# mysensor.net
KiCad netlist of a schematic drawn in EAGLE
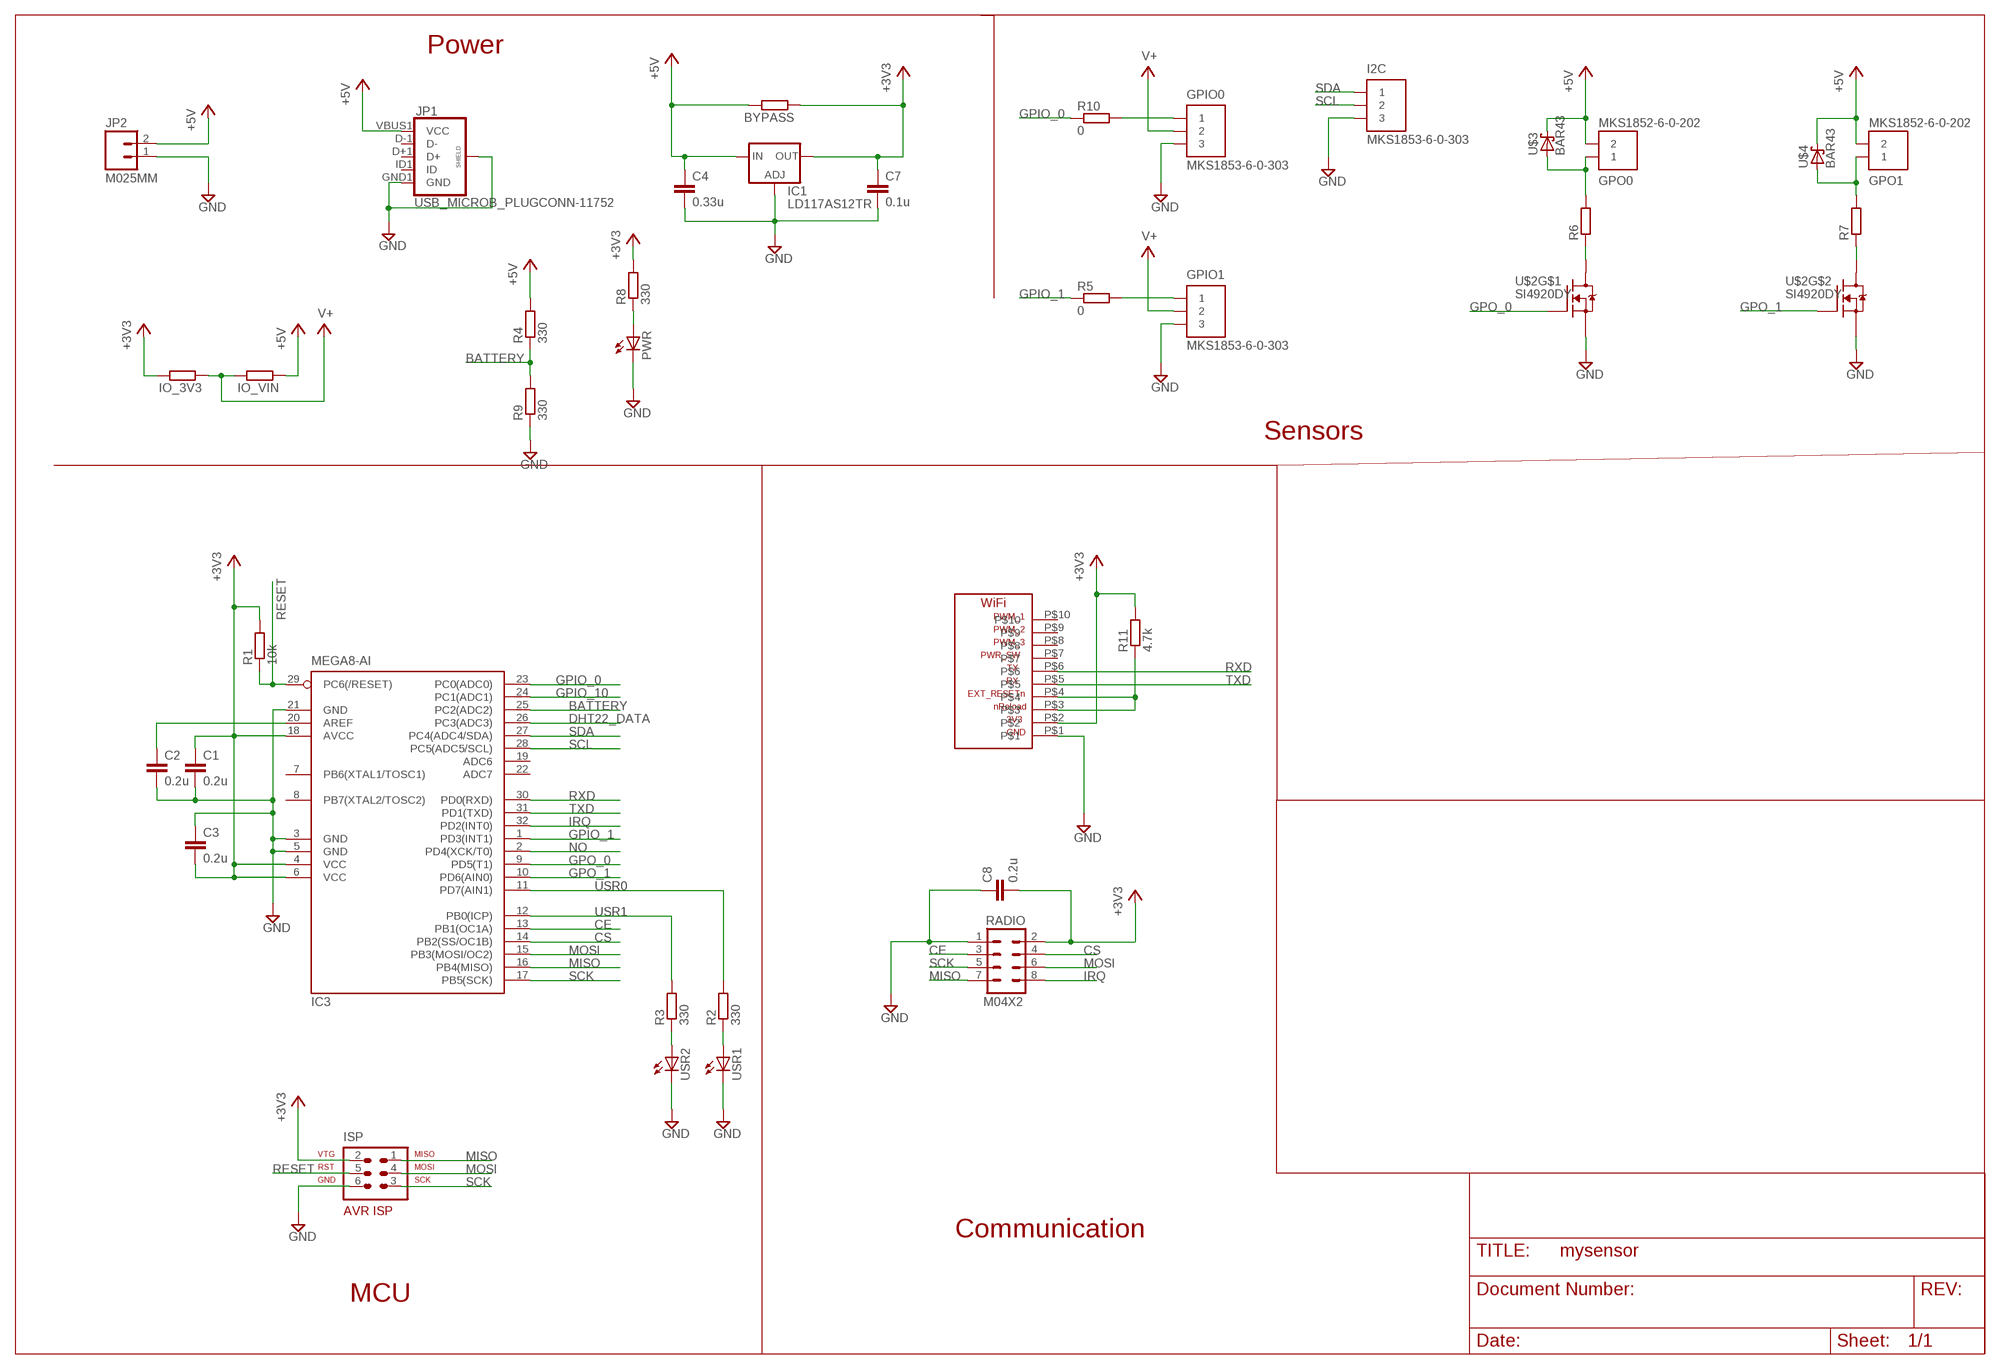
[diagram p0: schematic, sheet 1]

(export (version "E")
  (design (tool "Eeschema 10.0.6"))
  (components
    (comp (ref "BYPASS")
      (value "R-EU_M0805")
      (footprint "eagle-import:M0805")
      (libsource (lib "eagle-import") (part "R-EU_M0805"))
    )
    (comp (ref "C1")
      (value "0.2u")
      (footprint "eagle-import:C0805")
      (libsource (lib "eagle-import") (part "C-EUC0805"))
    )
    (comp (ref "C2")
      (value "0.2u")
      (footprint "eagle-import:C0805")
      (libsource (lib "eagle-import") (part "C-EUC0805"))
    )
    (comp (ref "C3")
      (value "0.2u")
      (footprint "eagle-import:C0805")
      (libsource (lib "eagle-import") (part "C-EUC0805"))
    )
    (comp (ref "C4")
      (value "0.33u")
      (footprint "eagle-import:C0805")
      (libsource (lib "eagle-import") (part "C-EUC0805"))
    )
    (comp (ref "C7")
      (value "0.1u")
      (footprint "eagle-import:C0805")
      (libsource (lib "eagle-import") (part "C-EUC0805"))
    )
    (comp (ref "C8")
      (value "0.2u")
      (footprint "eagle-import:C0805")
      (libsource (lib "eagle-import") (part "C-EUC0805"))
    )
    (comp (ref "GPIO0")
      (value "MKS1853-6-0-303")
      (footprint "eagle-import:MKS1853-6-0-303")
      (libsource (lib "eagle-import") (part "MKS1853-6-0-303"))
    )
    (comp (ref "GPIO1")
      (value "MKS1853-6-0-303")
      (footprint "eagle-import:MKS1853-6-0-303")
      (libsource (lib "eagle-import") (part "MKS1853-6-0-303"))
    )
    (comp (ref "GPO0")
      (value "MKS1852-6-0-202")
      (footprint "eagle-import:MKS1852-6-0-202")
      (libsource (lib "eagle-import") (part "MKS1852-6-0-202"))
    )
    (comp (ref "GPO1")
      (value "MKS1852-6-0-202")
      (footprint "eagle-import:MKS1852-6-0-202")
      (libsource (lib "eagle-import") (part "MKS1852-6-0-202"))
    )
    (comp (ref "I2C")
      (value "MKS1853-6-0-303")
      (footprint "eagle-import:MKS1853-6-0-303")
      (libsource (lib "eagle-import") (part "MKS1853-6-0-303"))
    )
    (comp (ref "IC1")
      (value "LD117AS12TR")
      (footprint "eagle-import:SOT223")
      (libsource (lib "eagle-import") (part "LD117A?S12TR"))
    )
    (comp (ref "IC3")
      (value "MEGA8-AI")
      (footprint "eagle-import:TQFP32-08")
      (fields (field (name "MPN") "ATMEGA8-16AU"))
      (libsource (lib "eagle-import") (part "MEGA8-AI"))
    )
    (comp (ref "IO_3V3")
      (value "R-EU_M0805")
      (footprint "eagle-import:M0805")
      (libsource (lib "eagle-import") (part "R-EU_M0805"))
    )
    (comp (ref "IO_VIN")
      (value "R-EU_M0805")
      (footprint "eagle-import:M0805")
      (libsource (lib "eagle-import") (part "R-EU_M0805"))
    )
    (comp (ref "ISP")
      (value "AVR-ISP-6")
      (footprint "eagle-import:AVR-ISP-6")
      (libsource (lib "eagle-import") (part "AVR-ISP-6"))
    )
    (comp (ref "JP1")
      (value "USB_MICROB_PLUGCONN-11752")
      (footprint "eagle-import:USB-B-MICRO-SMD_V03")
      (libsource (lib "eagle-import") (part "USB_MICROB_PLUGCONN-11752"))
    )
    (comp (ref "JP2")
      (value "M025MM")
      (footprint "eagle-import:SCREWTERMINAL-5MM-2")
      (libsource (lib "eagle-import") (part "M025MM"))
    )
    (comp (ref "PWR")
      (value "LEDCHIP-LED0805")
      (footprint "eagle-import:CHIP-LED0805")
      (libsource (lib "eagle-import") (part "LEDCHIP-LED0805"))
    )
    (comp (ref "R1")
      (value "10k")
      (footprint "eagle-import:R0805")
      (libsource (lib "eagle-import") (part "R-EU_R0805"))
    )
    (comp (ref "R2")
      (value "330")
      (footprint "eagle-import:M0805")
      (libsource (lib "eagle-import") (part "R-EU_M0805"))
    )
    (comp (ref "R3")
      (value "330")
      (footprint "eagle-import:M0805")
      (libsource (lib "eagle-import") (part "R-EU_M0805"))
    )
    (comp (ref "R4")
      (value "330")
      (footprint "eagle-import:M0805")
      (libsource (lib "eagle-import") (part "R-EU_M0805"))
    )
    (comp (ref "R5")
      (value "0")
      (footprint "eagle-import:R0805")
      (libsource (lib "eagle-import") (part "R-EU_R0805"))
    )
    (comp (ref "R6")
      (value "R-EU_M0805")
      (footprint "eagle-import:M0805")
      (libsource (lib "eagle-import") (part "R-EU_M0805"))
    )
    (comp (ref "R7")
      (value "R-EU_M0805")
      (footprint "eagle-import:M0805")
      (libsource (lib "eagle-import") (part "R-EU_M0805"))
    )
    (comp (ref "R8")
      (value "330")
      (footprint "eagle-import:M0805")
      (libsource (lib "eagle-import") (part "R-EU_M0805"))
    )
    (comp (ref "R9")
      (value "330")
      (footprint "eagle-import:M0805")
      (libsource (lib "eagle-import") (part "R-EU_M0805"))
    )
    (comp (ref "R10")
      (value "0")
      (footprint "eagle-import:R0805")
      (libsource (lib "eagle-import") (part "R-EU_R0805"))
    )
    (comp (ref "R11")
      (value "4.7k")
      (footprint "eagle-import:M0805")
      (libsource (lib "eagle-import") (part "R-EU_M0805"))
    )
    (comp (ref "RADIO")
      (value "M04X2")
      (footprint "eagle-import:2X4")
      (libsource (lib "eagle-import") (part "M04X2"))
    )
    (comp (ref "U$1")
      (value "WIFI232")
      (footprint "eagle-import:WLAN")
      (libsource (lib "eagle-import") (part "WIFI232"))
    )
    (comp (ref "U$2")
      (value "SI4920DY")
      (footprint "eagle-import:SO-8")
      (libsource (lib "eagle-import") (part "SI4920DY"))
    )
    (comp (ref "U$3")
      (value "BAR43")
      (footprint "eagle-import:SOT23")
      (libsource (lib "eagle-import") (part "BAR43"))
    )
    (comp (ref "U$4")
      (value "BAR43")
      (footprint "eagle-import:SOT23")
      (libsource (lib "eagle-import") (part "BAR43"))
    )
    (comp (ref "USR1")
      (value "LEDCHIP-LED0805")
      (footprint "eagle-import:CHIP-LED0805")
      (libsource (lib "eagle-import") (part "LEDCHIP-LED0805"))
    )
    (comp (ref "USR2")
      (value "LEDCHIP-LED0805")
      (footprint "eagle-import:CHIP-LED0805")
      (libsource (lib "eagle-import") (part "LEDCHIP-LED0805"))
    )
  )
  (nets
    (net (code "1") (name "+3V3") (class "Default")
      (node (ref "BYPASS") (pin "1") (pinfunction "1_1") (pintype "passive"))
      (node (ref "C1") (pin "1") (pinfunction "1_1") (pintype "passive"))
      (node (ref "C3") (pin "2") (pinfunction "2_2") (pintype "passive"))
      (node (ref "C7") (pin "1") (pinfunction "1_1") (pintype "passive"))
      (node (ref "C8") (pin "2") (pinfunction "2_2") (pintype "passive"))
      (node (ref "IC1") (pin "4") (pinfunction "OUT_4") (pintype "passive"))
      (node (ref "IC3") (pin "18") (pinfunction "AVCC_18") (pintype "power_in"))
      (node (ref "IC3") (pin "4") (pinfunction "VCC_4") (pintype "power_in"))
      (node (ref "IC3") (pin "6") (pinfunction "VCC_6") (pintype "power_in"))
      (node (ref "IO_3V3") (pin "2") (pinfunction "2_2") (pintype "passive"))
      (node (ref "ISP") (pin "2") (pinfunction "2_2") (pintype "passive"))
      (node (ref "R1") (pin "2") (pinfunction "2_2") (pintype "passive"))
      (node (ref "R11") (pin "2") (pinfunction "2_2") (pintype "passive"))
      (node (ref "R8") (pin "2") (pinfunction "2_2") (pintype "passive"))
      (node (ref "RADIO") (pin "2") (pinfunction "2_2") (pintype "passive"))
      (node (ref "U$1") (pin "P$2") (pinfunction "P$2_P$2") (pintype "bidirectional"))
    )
    (net (code "2") (name "+5V") (class "Default")
      (node (ref "BYPASS") (pin "2") (pinfunction "2_2") (pintype "passive"))
      (node (ref "C4") (pin "1") (pinfunction "1_1") (pintype "passive"))
      (node (ref "GPO0") (pin "2") (pinfunction "2_2") (pintype "input"))
      (node (ref "GPO1") (pin "2") (pinfunction "2_2") (pintype "input"))
      (node (ref "IC1") (pin "3") (pinfunction "IN_3") (pintype "input"))
      (node (ref "IO_VIN") (pin "1") (pinfunction "1_1") (pintype "passive"))
      (node (ref "JP1") (pin "VBUS1") (pinfunction "VCC_VBUS1") (pintype "bidirectional"))
      (node (ref "JP2") (pin "2") (pinfunction "2_2") (pintype "passive"))
      (node (ref "R4") (pin "2") (pinfunction "2_2") (pintype "passive"))
      (node (ref "U$3") (pin "3") (pinfunction "C_3") (pintype "passive"))
      (node (ref "U$4") (pin "3") (pinfunction "C_3") (pintype "passive"))
    )
    (net (code "3") (name "/BATTERY") (class "Default")
      (node (ref "IC3") (pin "25") (pinfunction "PC2(ADC2)_25") (pintype "bidirectional"))
      (node (ref "R4") (pin "1") (pinfunction "1_1") (pintype "passive"))
      (node (ref "R9") (pin "2") (pinfunction "2_2") (pintype "passive"))
    )
    (net (code "4") (name "/CE") (class "Default")
      (node (ref "IC3") (pin "13") (pinfunction "PB1(OC1A)_13") (pintype "bidirectional"))
      (node (ref "RADIO") (pin "3") (pinfunction "3_3") (pintype "passive"))
    )
    (net (code "5") (name "/CS") (class "Default")
      (node (ref "IC3") (pin "14") (pinfunction "PB2(SS/OC1B)_14") (pintype "bidirectional"))
      (node (ref "RADIO") (pin "4") (pinfunction "4_4") (pintype "passive"))
    )
    (net (code "6") (name "/DHT22_DATA") (class "Default")
      (node (ref "IC3") (pin "26") (pinfunction "PC3(ADC3)_26") (pintype "bidirectional"))
    )
    (net (code "7") (name "/GPIO_0") (class "Default")
      (node (ref "IC3") (pin "23") (pinfunction "PC0(ADC0)_23") (pintype "bidirectional"))
      (node (ref "R10") (pin "1") (pinfunction "1_1") (pintype "passive"))
    )
    (net (code "8") (name "/GPIO_1") (class "Default")
      (node (ref "IC3") (pin "1") (pinfunction "PD3(INT1)_1") (pintype "bidirectional"))
      (node (ref "R5") (pin "1") (pinfunction "1_1") (pintype "passive"))
    )
    (net (code "9") (name "/GPIO_10") (class "Default")
      (node (ref "IC3") (pin "24") (pinfunction "PC1(ADC1)_24") (pintype "bidirectional"))
    )
    (net (code "10") (name "/GPO_0") (class "Default")
      (node (ref "IC3") (pin "9") (pinfunction "PD5(T1)_9") (pintype "bidirectional"))
      (node (ref "U$2") (pin "2") (pinfunction "G_2") (pintype "passive"))
    )
    (net (code "11") (name "/GPO_1") (class "Default")
      (node (ref "IC3") (pin "10") (pinfunction "PD6(AIN0)_10") (pintype "bidirectional"))
      (node (ref "U$2") (pin "4") (pinfunction "G_4") (pintype "passive"))
    )
    (net (code "12") (name "/IRQ") (class "Default")
      (node (ref "IC3") (pin "32") (pinfunction "PD2(INT0)_32") (pintype "bidirectional"))
      (node (ref "RADIO") (pin "8") (pinfunction "8_8") (pintype "passive"))
    )
    (net (code "13") (name "/MISO") (class "Default")
      (node (ref "IC3") (pin "16") (pinfunction "PB4(MISO)_16") (pintype "bidirectional"))
      (node (ref "ISP") (pin "1") (pinfunction "1_1") (pintype "passive"))
      (node (ref "RADIO") (pin "7") (pinfunction "7_7") (pintype "passive"))
    )
    (net (code "14") (name "/MOSI") (class "Default")
      (node (ref "IC3") (pin "15") (pinfunction "PB3(MOSI/OC2)_15") (pintype "bidirectional"))
      (node (ref "ISP") (pin "4") (pinfunction "4_4") (pintype "passive"))
      (node (ref "RADIO") (pin "6") (pinfunction "6_6") (pintype "passive"))
    )
    (net (code "15") (name "/NO") (class "Default")
      (node (ref "IC3") (pin "2") (pinfunction "PD4(XCK/T0)_2") (pintype "bidirectional"))
    )
    (net (code "16") (name "/RESET") (class "Default")
      (node (ref "IC3") (pin "29") (pinfunction "PC6(/RESET)_29") (pintype "bidirectional"))
      (node (ref "ISP") (pin "5") (pinfunction "5_5") (pintype "passive"))
      (node (ref "R1") (pin "1") (pinfunction "1_1") (pintype "passive"))
    )
    (net (code "17") (name "/RXD") (class "Default")
      (node (ref "IC3") (pin "30") (pinfunction "PD0(RXD)_30") (pintype "bidirectional"))
      (node (ref "U$1") (pin "P$6") (pinfunction "P$6_P$6") (pintype "bidirectional"))
    )
    (net (code "18") (name "/SCK") (class "Default")
      (node (ref "IC3") (pin "17") (pinfunction "PB5(SCK)_17") (pintype "bidirectional"))
      (node (ref "ISP") (pin "3") (pinfunction "3_3") (pintype "passive"))
      (node (ref "RADIO") (pin "5") (pinfunction "5_5") (pintype "passive"))
    )
    (net (code "19") (name "/SCL") (class "Default")
      (node (ref "I2C") (pin "2") (pinfunction "2_2") (pintype "input"))
      (node (ref "IC3") (pin "28") (pinfunction "PC5(ADC5/SCL)_28") (pintype "bidirectional"))
    )
    (net (code "20") (name "/SDA") (class "Default")
      (node (ref "I2C") (pin "1") (pinfunction "1_1") (pintype "input"))
      (node (ref "IC3") (pin "27") (pinfunction "PC4(ADC4/SDA)_27") (pintype "bidirectional"))
    )
    (net (code "21") (name "/TXD") (class "Default")
      (node (ref "IC3") (pin "31") (pinfunction "PD1(TXD)_31") (pintype "bidirectional"))
      (node (ref "U$1") (pin "P$5") (pinfunction "P$5_P$5") (pintype "bidirectional"))
    )
    (net (code "22") (name "/USR0") (class "Default")
      (node (ref "IC3") (pin "11") (pinfunction "PD7(AIN1)_11") (pintype "bidirectional"))
      (node (ref "R2") (pin "2") (pinfunction "2_2") (pintype "passive"))
    )
    (net (code "23") (name "/USR1") (class "Default")
      (node (ref "IC3") (pin "12") (pinfunction "PB0(ICP)_12") (pintype "bidirectional"))
      (node (ref "R3") (pin "2") (pinfunction "2_2") (pintype "passive"))
    )
    (net (code "24") (name "GND") (class "Default")
      (node (ref "C1") (pin "2") (pinfunction "2_2") (pintype "passive"))
      (node (ref "C2") (pin "2") (pinfunction "2_2") (pintype "passive"))
      (node (ref "C3") (pin "1") (pinfunction "1_1") (pintype "passive"))
      (node (ref "C4") (pin "2") (pinfunction "2_2") (pintype "passive"))
      (node (ref "C7") (pin "2") (pinfunction "2_2") (pintype "passive"))
      (node (ref "C8") (pin "1") (pinfunction "1_1") (pintype "passive"))
      (node (ref "GPIO0") (pin "3") (pinfunction "3_3") (pintype "input"))
      (node (ref "GPIO1") (pin "3") (pinfunction "3_3") (pintype "input"))
      (node (ref "I2C") (pin "3") (pinfunction "3_3") (pintype "input"))
      (node (ref "IC1") (pin "1") (pinfunction "ADJ_1") (pintype "input"))
      (node (ref "IC3") (pin "21") (pinfunction "GND_21") (pintype "power_in"))
      (node (ref "IC3") (pin "3") (pinfunction "GND_3") (pintype "power_in"))
      (node (ref "IC3") (pin "5") (pinfunction "GND_5") (pintype "power_in"))
      (node (ref "ISP") (pin "6") (pinfunction "6_6") (pintype "passive"))
      (node (ref "JP1") (pin "GND1") (pinfunction "GND_GND1") (pintype "bidirectional"))
      (node (ref "JP1") (pin "SHIELD1") (pinfunction "SHIELD_SHIELD1") (pintype "bidirectional"))
      (node (ref "JP1") (pin "SHIELD2") (pinfunction "SHIELD_SHIELD2") (pintype "bidirectional"))
      (node (ref "JP1") (pin "SHIELD3") (pinfunction "SHIELD_SHIELD3") (pintype "bidirectional"))
      (node (ref "JP2") (pin "1") (pinfunction "1_1") (pintype "passive"))
      (node (ref "PWR") (pin "C") (pinfunction "C_C") (pintype "passive"))
      (node (ref "R9") (pin "1") (pinfunction "1_1") (pintype "passive"))
      (node (ref "RADIO") (pin "1") (pinfunction "1_1") (pintype "passive"))
      (node (ref "U$1") (pin "P$1") (pinfunction "P$1_P$1") (pintype "bidirectional"))
      (node (ref "U$2") (pin "1") (pinfunction "S_1") (pintype "passive"))
      (node (ref "U$2") (pin "3") (pinfunction "S_3") (pintype "passive"))
      (node (ref "USR1") (pin "C") (pinfunction "C_C") (pintype "passive"))
      (node (ref "USR2") (pin "C") (pinfunction "C_C") (pintype "passive"))
    )
    (net (code "25") (name "Net-(GPIO0-Pad1)") (class "Default")
      (node (ref "GPIO0") (pin "1") (pinfunction "1_1") (pintype "input"))
      (node (ref "R10") (pin "2") (pinfunction "2_2") (pintype "passive"))
    )
    (net (code "26") (name "Net-(GPIO1-Pad1)") (class "Default")
      (node (ref "GPIO1") (pin "1") (pinfunction "1_1") (pintype "input"))
      (node (ref "R5") (pin "2") (pinfunction "2_2") (pintype "passive"))
    )
    (net (code "27") (name "Net-(IC3-AREF)") (class "Default")
      (node (ref "C2") (pin "1") (pinfunction "1_1") (pintype "passive"))
      (node (ref "IC3") (pin "20") (pinfunction "AREF_20") (pintype "passive"))
    )
    (net (code "28") (name "Net-(PWR-PadA)") (class "Default")
      (node (ref "PWR") (pin "A") (pinfunction "A_A") (pintype "passive"))
      (node (ref "R8") (pin "1") (pinfunction "1_1") (pintype "passive"))
    )
    (net (code "29") (name "Net-(R2-Pad1)") (class "Default")
      (node (ref "R2") (pin "1") (pinfunction "1_1") (pintype "passive"))
      (node (ref "USR1") (pin "A") (pinfunction "A_A") (pintype "passive"))
    )
    (net (code "30") (name "Net-(R3-Pad1)") (class "Default")
      (node (ref "R3") (pin "1") (pinfunction "1_1") (pintype "passive"))
      (node (ref "USR2") (pin "A") (pinfunction "A_A") (pintype "passive"))
    )
    (net (code "31") (name "Net-(R11-Pad1)") (class "Default")
      (node (ref "R11") (pin "1") (pinfunction "1_1") (pintype "passive"))
      (node (ref "U$1") (pin "P$3") (pinfunction "P$3_P$3") (pintype "bidirectional"))
      (node (ref "U$1") (pin "P$4") (pinfunction "P$4_P$4") (pintype "bidirectional"))
    )
    (net (code "32") (name "Net-(U$2A-D1)") (class "Default")
      (node (ref "R6") (pin "1") (pinfunction "1_1") (pintype "passive"))
      (node (ref "U$2") (pin "7") (pinfunction "D1_7") (pintype "passive"))
    )
    (net (code "33") (name "Net-(U$2B-D1)") (class "Default")
      (node (ref "R7") (pin "1") (pinfunction "1_1") (pintype "passive"))
      (node (ref "U$2") (pin "5") (pinfunction "D1_5") (pintype "passive"))
    )
    (net (code "34") (name "Net-(U$3-A)") (class "Default")
      (node (ref "GPO0") (pin "1") (pinfunction "1_1") (pintype "input"))
      (node (ref "R6") (pin "2") (pinfunction "2_2") (pintype "passive"))
      (node (ref "U$3") (pin "1") (pinfunction "A_1") (pintype "passive"))
    )
    (net (code "35") (name "Net-(U$4-A)") (class "Default")
      (node (ref "GPO1") (pin "1") (pinfunction "1_1") (pintype "input"))
      (node (ref "R7") (pin "2") (pinfunction "2_2") (pintype "passive"))
      (node (ref "U$4") (pin "1") (pinfunction "A_1") (pintype "passive"))
    )
    (net (code "36") (name "V+") (class "Default")
      (node (ref "GPIO0") (pin "2") (pinfunction "2_2") (pintype "input"))
      (node (ref "GPIO1") (pin "2") (pinfunction "2_2") (pintype "input"))
      (node (ref "IO_3V3") (pin "1") (pinfunction "1_1") (pintype "passive"))
      (node (ref "IO_VIN") (pin "2") (pinfunction "2_2") (pintype "passive"))
    )
    (net (code "37") (name "unconnected-(IC3-ADC6-Pad19)") (class "Default")
      (node (ref "IC3") (pin "19") (pinfunction "ADC6_19") (pintype "bidirectional"))
    )
    (net (code "38") (name "unconnected-(IC3-ADC7-Pad22)") (class "Default")
      (node (ref "IC3") (pin "22") (pinfunction "ADC7_22") (pintype "bidirectional"))
    )
    (net (code "39") (name "unconnected-(IC3-PB6(XTAL1{slash}TOSC1)-Pad7)") (class "Default")
      (node (ref "IC3") (pin "7") (pinfunction "PB6(XTAL1/TOSC1)_7") (pintype "bidirectional"))
    )
    (net (code "40") (name "unconnected-(IC3-PB7(XTAL2{slash}TOSC2)-Pad8)") (class "Default")
      (node (ref "IC3") (pin "8") (pinfunction "PB7(XTAL2/TOSC2)_8") (pintype "bidirectional"))
    )
    (net (code "41") (name "unconnected-(JP1-D+-PadD+1)") (class "Default")
      (node (ref "JP1") (pin "D+1") (pinfunction "D+_D+1") (pintype "bidirectional"))
    )
    (net (code "42") (name "unconnected-(JP1-D--PadD-1)") (class "Default")
      (node (ref "JP1") (pin "D-1") (pinfunction "D-_D-1") (pintype "bidirectional"))
    )
    (net (code "43") (name "unconnected-(JP1-ID-PadID1)") (class "Default")
      (node (ref "JP1") (pin "ID1") (pinfunction "ID_ID1") (pintype "bidirectional"))
    )
    (net (code "44") (name "unconnected-(U$1-PadP$7)") (class "Default")
      (node (ref "U$1") (pin "P$7") (pinfunction "P$7_P$7") (pintype "bidirectional"))
    )
    (net (code "45") (name "unconnected-(U$1-PadP$8)") (class "Default")
      (node (ref "U$1") (pin "P$8") (pinfunction "P$8_P$8") (pintype "bidirectional"))
    )
    (net (code "46") (name "unconnected-(U$1-PadP$9)") (class "Default")
      (node (ref "U$1") (pin "P$9") (pinfunction "P$9_P$9") (pintype "bidirectional"))
    )
    (net (code "47") (name "unconnected-(U$1-PadP$10)") (class "Default")
      (node (ref "U$1") (pin "P$10") (pinfunction "P$10_P$10") (pintype "bidirectional"))
    )
    (net (code "48") (name "unconnected-(U$2A-D-Pad8)") (class "Default")
      (node (ref "U$2") (pin "8") (pinfunction "D_8") (pintype "passive"))
    )
    (net (code "49") (name "unconnected-(U$2B-D-Pad6)") (class "Default")
      (node (ref "U$2") (pin "6") (pinfunction "D_6") (pintype "passive"))
    )
  )
)
